# microbean.net
KiCad netlist of a schematic drawn in EAGLE
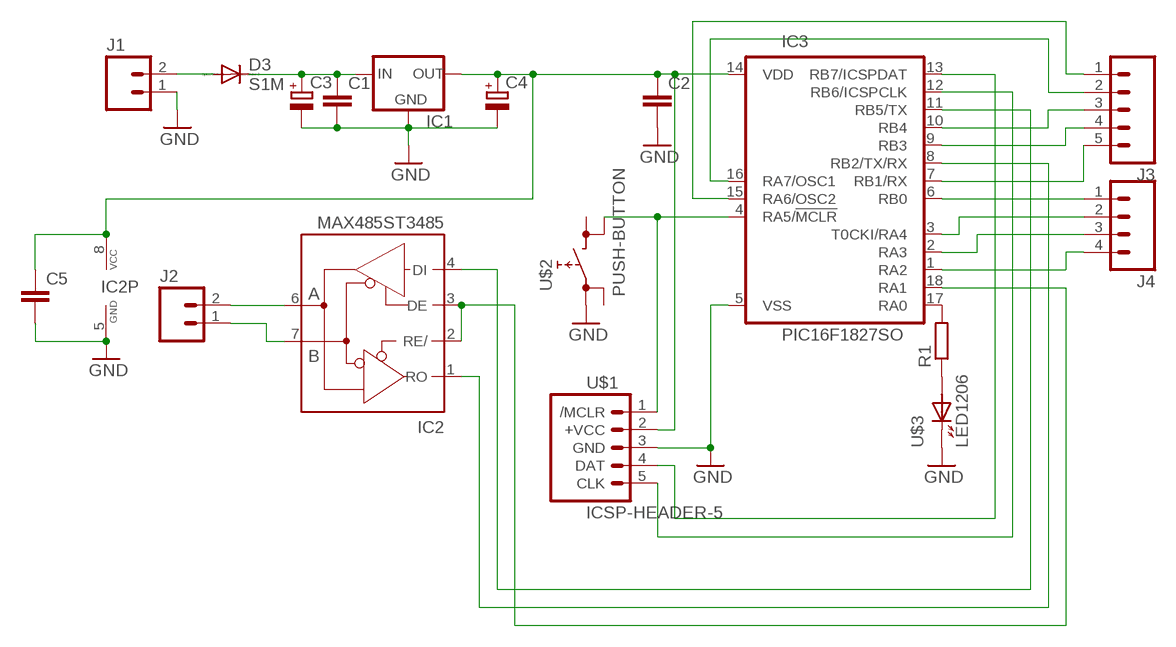
[diagram p0: schematic, sheet 1]

(export (version "E")
  (design (tool "Eeschema 10.0.6"))
  (components
    (comp (ref "C1")
      (value "C-EUC0805")
      (footprint "eagle-import:C0805")
      (libsource (lib "eagle-import") (part "C-EUC0805"))
    )
    (comp (ref "C2")
      (value "C-EUC0805")
      (footprint "eagle-import:C0805")
      (libsource (lib "eagle-import") (part "C-EUC0805"))
    )
    (comp (ref "C3")
      (value "CPOL-EUSMD4X5.3")
      (footprint "eagle-import:UD-4X5,8_NICHICON")
      (libsource (lib "eagle-import") (part "CPOL-EUSMD4X5.3"))
    )
    (comp (ref "C4")
      (value "CPOL-EUSMD4X5.3")
      (footprint "eagle-import:UD-4X5,8_NICHICON")
      (libsource (lib "eagle-import") (part "CPOL-EUSMD4X5.3"))
    )
    (comp (ref "C5")
      (value "C-EUC0805")
      (footprint "eagle-import:C0805")
      (libsource (lib "eagle-import") (part "C-EUC0805"))
    )
    (comp (ref "D3")
      (value "S1M")
      (footprint "eagle-import:SMA")
      (libsource (lib "eagle-import") (part "S1M"))
    )
    (comp (ref "IC1")
      (value "78LXXSOT89")
      (footprint "eagle-import:SOT89")
      (libsource (lib "eagle-import") (part "78LXXSOT89"))
    )
    (comp (ref "IC2")
      (value "MAX485ST3485")
      (footprint "eagle-import:SO08")
      (libsource (lib "eagle-import") (part "MAX485ST3485"))
    )
    (comp (ref "IC3")
      (value "PIC16F1827SO")
      (footprint "eagle-import:SO-18W")
      (libsource (lib "eagle-import") (part "PIC16F1827SO"))
    )
    (comp (ref "J1")
      (value "M02-SCREW-3.5MM3.5MM")
      (footprint "eagle-import:SCREWTERMINAL-3.5MM-2")
      (libsource (lib "eagle-import") (part "M02-SCREW-3.5MM3.5MM"))
    )
    (comp (ref "J2")
      (value "M02-SCREW-3.5MM3.5MM")
      (footprint "eagle-import:SCREWTERMINAL-3.5MM-2")
      (libsource (lib "eagle-import") (part "M02-SCREW-3.5MM3.5MM"))
    )
    (comp (ref "J3")
      (value "M05PTH")
      (footprint "eagle-import:1X05")
      (libsource (lib "eagle-import") (part "M05PTH"))
    )
    (comp (ref "J4")
      (value "M04")
      (footprint "eagle-import:1X04")
      (libsource (lib "eagle-import") (part "M04"))
    )
    (comp (ref "R1")
      (value "R-EU_R0805")
      (footprint "eagle-import:R0805")
      (libsource (lib "eagle-import") (part "R-EU_R0805"))
    )
    (comp (ref "U$1")
      (value "ICSP-HEADER-5")
      (footprint "eagle-import:1X05")
      (libsource (lib "eagle-import") (part "ICSP-HEADER-5"))
    )
    (comp (ref "U$2")
      (value "PUSH-BUTTON")
      (footprint "eagle-import:MICRO-SWITCH")
      (libsource (lib "eagle-import") (part "PUSH-BUTTON"))
    )
    (comp (ref "U$3")
      (value "LED1206")
      (footprint "eagle-import:CHIPLED_1206")
      (libsource (lib "eagle-import") (part "LED1206"))
    )
  )
  (nets
    (net (code "1") (name "GND") (class "Default")
      (node (ref "C1") (pin "2") (pinfunction "2_2") (pintype "passive"))
      (node (ref "C2") (pin "2") (pinfunction "2_2") (pintype "passive"))
      (node (ref "C3") (pin "-") (pinfunction "-_-") (pintype "passive"))
      (node (ref "C4") (pin "-") (pinfunction "-_-") (pintype "passive"))
      (node (ref "C5") (pin "2") (pinfunction "2_2") (pintype "passive"))
      (node (ref "IC1") (pin "2") (pinfunction "GND_2") (pintype "input"))
      (node (ref "IC2") (pin "5") (pinfunction "GND_5") (pintype "power_in"))
      (node (ref "IC3") (pin "5") (pinfunction "VSS_5") (pintype "power_in"))
      (node (ref "J1") (pin "1") (pinfunction "1_1") (pintype "passive"))
      (node (ref "U$1") (pin "3") (pinfunction "GND_3") (pintype "passive"))
      (node (ref "U$2") (pin "1") (pinfunction "0_1") (pintype "passive"))
      (node (ref "U$3") (pin "C") (pinfunction "K_C") (pintype "passive"))
    )
    (net (code "2") (name "Net-(D3-PadA)") (class "Default")
      (node (ref "D3") (pin "A") (pinfunction "A_A") (pintype "passive"))
      (node (ref "J1") (pin "2") (pinfunction "2_2") (pintype "passive"))
    )
    (net (code "3") (name "Net-(IC1-IN)") (class "Default")
      (node (ref "C1") (pin "1") (pinfunction "1_1") (pintype "passive"))
      (node (ref "C3") (pin "+") (pinfunction "+_+") (pintype "passive"))
      (node (ref "D3") (pin "C") (pinfunction "C_C") (pintype "passive"))
      (node (ref "IC1") (pin "3") (pinfunction "IN_3") (pintype "input"))
    )
    (net (code "4") (name "Net-(IC1-OUT)") (class "Default")
      (node (ref "C2") (pin "1") (pinfunction "1_1") (pintype "passive"))
      (node (ref "C4") (pin "+") (pinfunction "+_+") (pintype "passive"))
      (node (ref "C5") (pin "1") (pinfunction "1_1") (pintype "passive"))
      (node (ref "IC1") (pin "1") (pinfunction "OUT_1") (pintype "passive"))
      (node (ref "IC2") (pin "8") (pinfunction "VCC_8") (pintype "power_in"))
      (node (ref "IC3") (pin "14") (pinfunction "VDD_14") (pintype "power_in"))
      (node (ref "U$1") (pin "2") (pinfunction "+VCC_2") (pintype "passive"))
    )
    (net (code "5") (name "Net-(IC2A-A)") (class "Default")
      (node (ref "IC2") (pin "6") (pinfunction "A_6") (pintype "passive"))
      (node (ref "J2") (pin "2") (pinfunction "2_2") (pintype "passive"))
    )
    (net (code "6") (name "Net-(IC2A-B)") (class "Default")
      (node (ref "IC2") (pin "7") (pinfunction "B_7") (pintype "passive"))
      (node (ref "J2") (pin "1") (pinfunction "1_1") (pintype "passive"))
    )
    (net (code "7") (name "Net-(IC2A-DE)") (class "Default")
      (node (ref "IC2") (pin "2") (pinfunction "RE/_2") (pintype "input"))
      (node (ref "IC2") (pin "3") (pinfunction "DE_3") (pintype "input"))
      (node (ref "IC3") (pin "18") (pinfunction "RA1_18") (pintype "bidirectional"))
    )
    (net (code "8") (name "Net-(IC2A-DI)") (class "Default")
      (node (ref "IC2") (pin "4") (pinfunction "DI_4") (pintype "input"))
      (node (ref "IC3") (pin "11") (pinfunction "RB5/TX_11") (pintype "bidirectional"))
    )
    (net (code "9") (name "Net-(IC2A-RO)") (class "Default")
      (node (ref "IC2") (pin "1") (pinfunction "RO_1") (pintype "output"))
      (node (ref "IC3") (pin "8") (pinfunction "RB2/TX/RX_8") (pintype "bidirectional"))
    )
    (net (code "10") (name "Net-(IC3-RA0)") (class "Default")
      (node (ref "IC3") (pin "17") (pinfunction "RA0_17") (pintype "bidirectional"))
      (node (ref "R1") (pin "2") (pinfunction "2_2") (pintype "passive"))
    )
    (net (code "11") (name "Net-(IC3-RA2)") (class "Default")
      (node (ref "IC3") (pin "1") (pinfunction "RA2_1") (pintype "bidirectional"))
      (node (ref "J4") (pin "4") (pinfunction "4_4") (pintype "passive"))
    )
    (net (code "12") (name "Net-(IC3-RA3)") (class "Default")
      (node (ref "IC3") (pin "2") (pinfunction "RA3_2") (pintype "bidirectional"))
      (node (ref "J4") (pin "3") (pinfunction "3_3") (pintype "passive"))
    )
    (net (code "13") (name "Net-(IC3-RA5{slash}~{MCLR})") (class "Default")
      (node (ref "IC3") (pin "4") (pinfunction "RA5/~{MCLR}_4") (pintype "input"))
      (node (ref "U$1") (pin "1") (pinfunction "/MCLR_1") (pintype "passive"))
      (node (ref "U$2") (pin "4") (pinfunction "1_4") (pintype "passive"))
    )
    (net (code "14") (name "Net-(IC3-RA6{slash}OSC2)") (class "Default")
      (node (ref "IC3") (pin "15") (pinfunction "RA6/OSC2_15") (pintype "output"))
      (node (ref "J3") (pin "1") (pinfunction "1_1") (pintype "passive"))
    )
    (net (code "15") (name "Net-(IC3-RA7{slash}OSC1)") (class "Default")
      (node (ref "IC3") (pin "16") (pinfunction "RA7/OSC1_16") (pintype "input"))
      (node (ref "J3") (pin "2") (pinfunction "2_2") (pintype "passive"))
    )
    (net (code "16") (name "Net-(IC3-RB0)") (class "Default")
      (node (ref "IC3") (pin "6") (pinfunction "RB0_6") (pintype "bidirectional"))
      (node (ref "J4") (pin "1") (pinfunction "1_1") (pintype "passive"))
    )
    (net (code "17") (name "Net-(IC3-RB1{slash}RX)") (class "Default")
      (node (ref "IC3") (pin "7") (pinfunction "RB1/RX_7") (pintype "bidirectional"))
      (node (ref "J3") (pin "5") (pinfunction "5_5") (pintype "passive"))
    )
    (net (code "18") (name "Net-(IC3-RB3)") (class "Default")
      (node (ref "IC3") (pin "9") (pinfunction "RB3_9") (pintype "bidirectional"))
      (node (ref "J3") (pin "4") (pinfunction "4_4") (pintype "passive"))
    )
    (net (code "19") (name "Net-(IC3-RB4)") (class "Default")
      (node (ref "IC3") (pin "10") (pinfunction "RB4_10") (pintype "bidirectional"))
      (node (ref "J3") (pin "3") (pinfunction "3_3") (pintype "passive"))
    )
    (net (code "20") (name "Net-(IC3-RB6{slash}ICSPCLK)") (class "Default")
      (node (ref "IC3") (pin "12") (pinfunction "RB6/ICSPCLK_12") (pintype "bidirectional"))
      (node (ref "U$1") (pin "5") (pinfunction "CLK_5") (pintype "passive"))
    )
    (net (code "21") (name "Net-(IC3-RB7{slash}ICSPDAT)") (class "Default")
      (node (ref "IC3") (pin "13") (pinfunction "RB7/ICSPDAT_13") (pintype "bidirectional"))
      (node (ref "U$1") (pin "4") (pinfunction "DAT_4") (pintype "passive"))
    )
    (net (code "22") (name "Net-(IC3-T0CKI{slash}RA4)") (class "Default")
      (node (ref "IC3") (pin "3") (pinfunction "T0CKI/RA4_3") (pintype "bidirectional"))
      (node (ref "J4") (pin "2") (pinfunction "2_2") (pintype "passive"))
    )
    (net (code "23") (name "Net-(R1-Pad1)") (class "Default")
      (node (ref "R1") (pin "1") (pinfunction "1_1") (pintype "passive"))
      (node (ref "U$3") (pin "A") (pinfunction "A_A") (pintype "passive"))
    )
    (net (code "24") (name "unconnected-(U$2-0-Pad2)") (class "Default")
      (node (ref "U$2") (pin "2") (pinfunction "0_2") (pintype "passive"))
    )
    (net (code "25") (name "unconnected-(U$2-1-Pad3)") (class "Default")
      (node (ref "U$2") (pin "3") (pinfunction "1_3") (pintype "passive"))
    )
  )
)
